# presure_sensor.net
KiCad netlist of a schematic drawn in Altium Designer
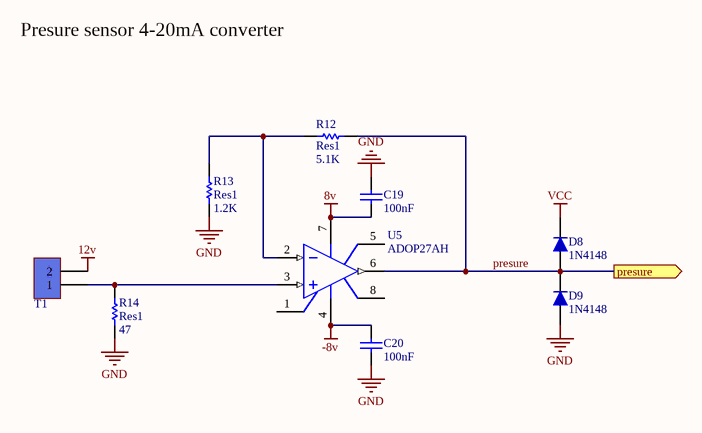
[diagram p0: presure_sensor.SchDoc]

(export (version "E")
  (design (tool "Eeschema 10.0.6"))
  (components
    (comp (ref "C19")
      (value "100nF")
      (footprint "CAP 1206 (3216X15L)")
      (description "CAP-100Nf")
      (fields (field (name "Comment") "Cap"))
      (libsource (lib "Altium library (www.AVRelec.com)") (part "Cap ceramic"))
    )
    (comp (ref "C20")
      (value "100nF")
      (footprint "CAP 1206 (3216X15L)")
      (description "CAP-100Nf")
      (fields (field (name "Comment") "Cap"))
      (libsource (lib "Altium library (www.AVRelec.com)") (part "Cap ceramic"))
    )
    (comp (ref "D8")
      (value "1N4148")
      (footprint "LL4148")
      (description "DIODE GEN PURP 100V 200MA DO35")
      (fields (field (name "PUBLISHER") "Abbas Basereh"))
      (libsource (lib "Altium (2)") (part "1N4148"))
    )
    (comp (ref "D9")
      (value "1N4148")
      (footprint "LL4148")
      (description "DIODE GEN PURP 100V 200MA DO35")
      (fields (field (name "PUBLISHER") "Abbas Basereh"))
      (libsource (lib "Altium (2)") (part "1N4148"))
    )
    (comp (ref "R12")
      (value "Res1")
      (footprint "RES 1206 (3216X08L)")
      (description "Resistor")
      (fields (field (name "ALTIUM_VALUE") "5.1K") (field (name "PUBLISHER") "Altium Limited"))
      (libsource (lib "Miscellaneous Devices") (part "Res1"))
    )
    (comp (ref "R13")
      (value "Res1")
      (footprint "RES 1206 (3216X08L)")
      (description "Resistor")
      (fields (field (name "ALTIUM_VALUE") "1.2K") (field (name "PUBLISHER") "Altium Limited"))
      (libsource (lib "Miscellaneous Devices") (part "Res1"))
    )
    (comp (ref "R14")
      (value "Res1")
      (footprint "RES 1206 (3216X08L)")
      (description "Resistor")
      (fields (field (name "ALTIUM_VALUE") "47") (field (name "PUBLISHER") "Altium Limited"))
      (libsource (lib "Miscellaneous Devices") (part "Res1"))
    )
    (comp (ref "T1")
      (value "Terminal")
      (footprint "Terminal 1*2")
      (description "Terminal 2 Pin 250VAC 16A")
      (fields (field (name "DESIGNER") "Seyed Mohsen Ghasemain") (field (name "E-MAIL") "picpars@gmail.com"))
      (libsource (lib "PicPars.com_usefully_Library") (part "Terminal 1*2"))
    )
    (comp (ref "U5")
      (value "ADOP27AH")
      (footprint "SOIC8-Narrow")
      (description "Ultra-Low Noise, Precision Operational Amplifier")
      (fields (field (name "PUBLISHER") "Altium Limited"))
      (libsource (lib "AD Operational Amplifier") (part "ADOP27AH"))
    )
  )
  (nets
    (net (code "1") (name "-8v") (class "Default")
      (node (ref "C20") (pin "2") (pinfunction "2_2") (pintype "passive"))
      (node (ref "U5") (pin "4") (pinfunction "V-_4") (pintype "power_in"))
    )
    (net (code "2") (name "/presure") (class "Default")
      (node (ref "D8") (pin "1") (pintype "passive"))
      (node (ref "D9") (pin "2") (pintype "passive"))
      (node (ref "R12") (pin "2") (pinfunction "2_2") (pintype "passive"))
      (node (ref "U5") (pin "6") (pinfunction "OUT_6") (pintype "output"))
    )
    (net (code "3") (name "8v") (class "Default")
      (node (ref "C19") (pin "1") (pinfunction "1_1") (pintype "passive"))
      (node (ref "U5") (pin "7") (pinfunction "V+_7") (pintype "power_in"))
    )
    (net (code "4") (name "12v") (class "Default")
      (node (ref "T1") (pin "2") (pinfunction "2_2") (pintype "passive"))
    )
    (net (code "5") (name "GND") (class "Default")
      (node (ref "C19") (pin "2") (pinfunction "2_2") (pintype "passive"))
      (node (ref "C20") (pin "1") (pinfunction "1_1") (pintype "passive"))
      (node (ref "D9") (pin "1") (pintype "passive"))
      (node (ref "R13") (pin "1") (pinfunction "1_1") (pintype "passive"))
      (node (ref "R14") (pin "1") (pinfunction "1_1") (pintype "passive"))
    )
    (net (code "6") (name "Net-(U5-IN+)") (class "Default")
      (node (ref "R14") (pin "2") (pinfunction "2_2") (pintype "passive"))
      (node (ref "T1") (pin "1") (pinfunction "1_1") (pintype "passive"))
      (node (ref "U5") (pin "3") (pinfunction "IN+_3") (pintype "input"))
    )
    (net (code "7") (name "Net-(U5-IN-)") (class "Default")
      (node (ref "R12") (pin "1") (pinfunction "1_1") (pintype "passive"))
      (node (ref "R13") (pin "2") (pinfunction "2_2") (pintype "passive"))
      (node (ref "U5") (pin "2") (pinfunction "IN-_2") (pintype "input"))
    )
    (net (code "8") (name "VCC") (class "Default") (node (ref "D8") (pin "2") (pintype "passive")))
    (net (code "9") (name "unconnected-(U5-NC-Pad5)") (class "Default")
      (node (ref "U5") (pin "5") (pinfunction "NC_5") (pintype "passive"))
    )
    (net (code "10") (name "unconnected-(U5-OS_NULL-Pad1)") (class "Default")
      (node (ref "U5") (pin "1") (pinfunction "OS_NULL_1") (pintype "passive"))
    )
    (net (code "11") (name "unconnected-(U5-OS_NULL-Pad8)") (class "Default")
      (node (ref "U5") (pin "8") (pinfunction "OS_NULL_8") (pintype "passive"))
    )
  )
)
